# BenchExam.net
KiCad netlist of a schematic drawn in Altium Designer
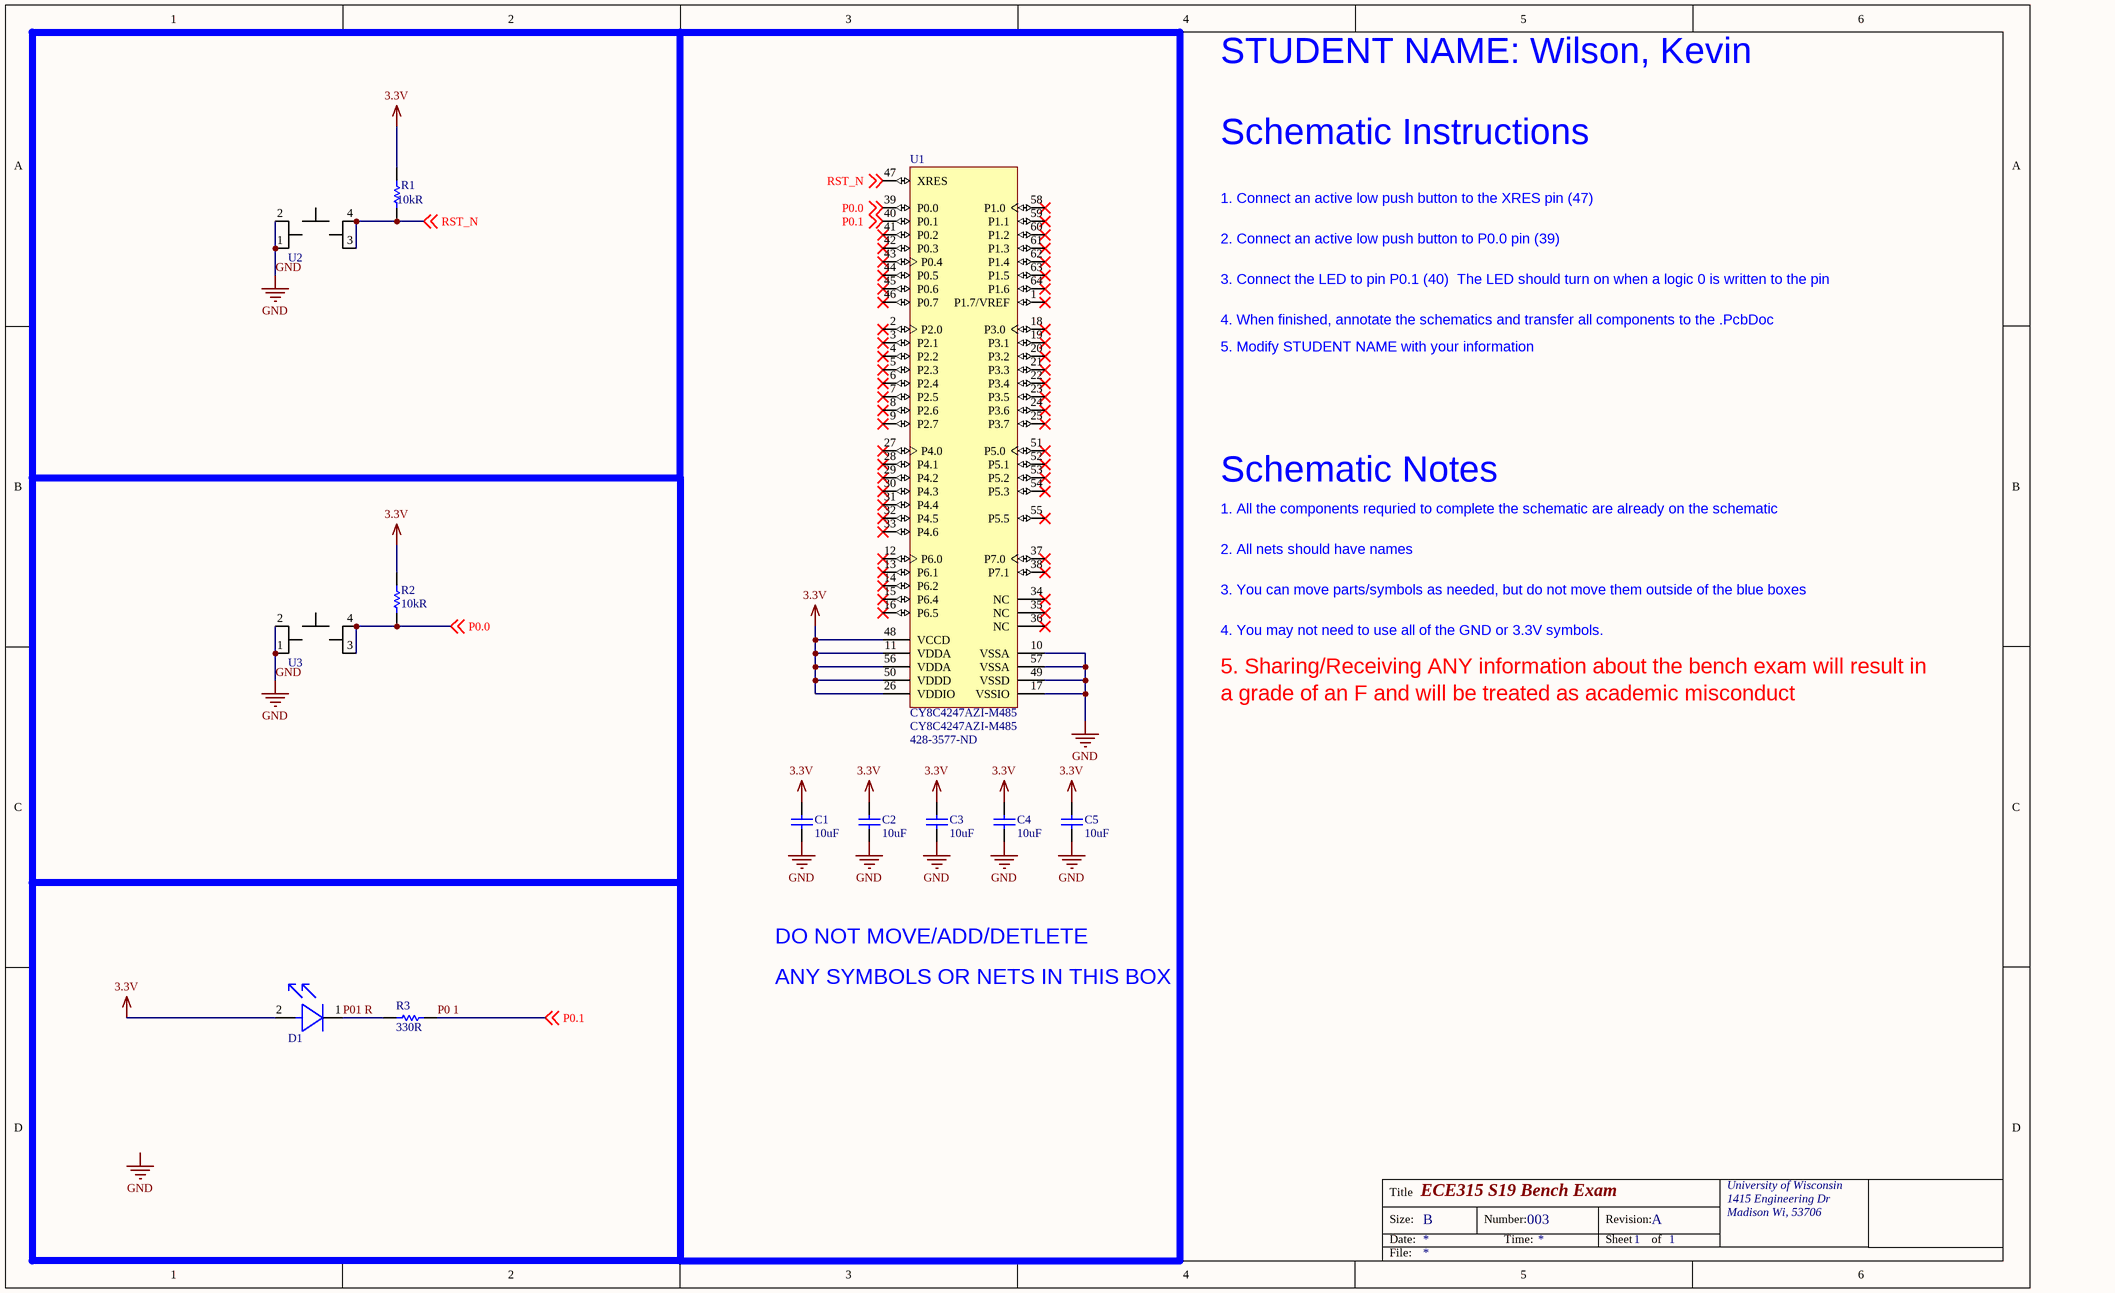
[diagram p0: BenchExam.SchDoc]

(export (version "E")
  (design (tool "Eeschema 10.0.6"))
  (components
    (comp (ref "C1")
      (value "10uF")
      (footprint "CAP_0805")
      (description "CAP CER 10UF 16V X7R 0805")
      (fields
        (field (name "TOLERANCE") "10%")
        (field (name "MANUFACTURER") "Samsung")
        (field (name "CAPACITANCE") "10uF")
      )
      (libsource (lib "BenchExam") (part "CAP_0805_U_010.00"))
    )
    (comp (ref "C2")
      (value "10uF")
      (footprint "CAP_0805")
      (description "CAP CER 10UF 16V X7R 0805")
      (fields
        (field (name "TOLERANCE") "10%")
        (field (name "MANUFACTURER") "Samsung")
        (field (name "CAPACITANCE") "10uF")
      )
      (libsource (lib "BenchExam") (part "CAP_0805_U_010.00"))
    )
    (comp (ref "C3")
      (value "10uF")
      (footprint "CAP_0805")
      (description "CAP CER 10UF 16V X7R 0805")
      (fields
        (field (name "TOLERANCE") "10%")
        (field (name "MANUFACTURER") "Samsung")
        (field (name "CAPACITANCE") "10uF")
      )
      (libsource (lib "BenchExam") (part "CAP_0805_U_010.00"))
    )
    (comp (ref "C4")
      (value "10uF")
      (footprint "CAP_0805")
      (description "CAP CER 10UF 16V X7R 0805")
      (fields
        (field (name "TOLERANCE") "10%")
        (field (name "MANUFACTURER") "Samsung")
        (field (name "CAPACITANCE") "10uF")
      )
      (libsource (lib "BenchExam") (part "CAP_0805_U_010.00"))
    )
    (comp (ref "C5")
      (value "10uF")
      (footprint "CAP_0805")
      (description "CAP CER 10UF 16V X7R 0805")
      (fields
        (field (name "TOLERANCE") "10%")
        (field (name "MANUFACTURER") "Samsung")
        (field (name "CAPACITANCE") "10uF")
      )
      (libsource (lib "BenchExam") (part "CAP_0805_U_010.00"))
    )
    (comp (ref "D1")
      (value "LED_BLUE_0805.1")
      (footprint "LED_BLU_0805")
      (description "LED 468NM BLUE CLEAR 0805 SMD")
      (fields
        (field (name "MANUFACTURER") "Vishay Lite-On")
        (field (name "MANUFACTURER PART NUMBER") "LTST-C171TBKT")
      )
      (libsource (lib "BenchExam") (part "LED_BLUE_0805.1"))
    )
    (comp (ref "R1")
      (value "10K")
      (footprint "RES_0805")
      (description "RES SMD 10K OHM 1% 1/8W 0805")
      (fields
        (field (name "MANUFACTURER PART NUMBER") "RMCF0805FT10K0")
        (field (name "TOLERANCE") "1%")
        (field (name "RESISTANCE") "10kR")
      )
      (libsource (lib "BenchExam") (part "RES_0805_K_010.00"))
    )
    (comp (ref "R2")
      (value "10K")
      (footprint "RES_0805")
      (description "RES SMD 10K OHM 1% 1/8W 0805")
      (fields
        (field (name "MANUFACTURER PART NUMBER") "RMCF0805FT10K0")
        (field (name "TOLERANCE") "1%")
        (field (name "RESISTANCE") "10kR")
      )
      (libsource (lib "BenchExam") (part "RES_0805_K_010.00"))
    )
    (comp (ref "R3")
      (value "330")
      (footprint "RES_0805")
      (description "RES SMD 330 OHM 1% 1/8W 0805")
      (fields
        (field (name "MANUFACTURER") "Stackpole Electronics")
        (field (name "MANUFACTURER PART NUMBER") "RMCF0805FT330R")
        (field (name "RESISTANCE") "330R")
      )
      (libsource (lib "BenchExam") (part "RES_0805_R_330.00"))
    )
    (comp (ref "U1")
      (value "CY8C4247AZI-M485")
      (footprint "CYP-AZ64_N")
      (fields
        (field (name "MANUFACTURER") "Cypress")
        (field (name "MANUFACTURER PART NUMBER") "CY8C4247AZI-M485")
        (field (name "SUPPLIER PART NUMBER") "428-3577-ND")
      )
      (libsource (lib "BenchExam") (part "CY8C4247AZI-M485"))
    )
    (comp (ref "U2")
      (value "SWITCH_6mm_6mm_smd")
      (footprint "SWITCH_6mm_6mm_smd")
      (description "SWITCH TACTILE SPST-NO 0.05A 12V")
      (fields
        (field (name "MANUFACTURER") "Carl Kammerling")
        (field (name "MANUFACTURER PART NUMBER") "PTS645SH50SMTR92LFS")
      )
      (libsource (lib "BenchExam") (part "SWITCH_6mm_6mm_smd"))
    )
    (comp (ref "U3")
      (value "SWITCH_6mm_6mm_smd")
      (footprint "SWITCH_6mm_6mm_smd")
      (description "SWITCH TACTILE SPST-NO 0.05A 12V")
      (fields
        (field (name "MANUFACTURER") "Carl Kammerling")
        (field (name "MANUFACTURER PART NUMBER") "PTS645SH50SMTR92LFS")
      )
      (libsource (lib "BenchExam") (part "SWITCH_6mm_6mm_smd"))
    )
  )
  (nets
    (net (code "1") (name "/P01 R") (class "Default")
      (node (ref "D1") (pin "1") (pinfunction "Cathode_1") (pintype "passive"))
      (node (ref "R3") (pin "1") (pinfunction "1_1") (pintype "passive"))
    )
    (net (code "2") (name "3.3V") (class "Default")
      (node (ref "C1") (pin "2") (pinfunction "2_2") (pintype "passive"))
      (node (ref "C2") (pin "2") (pinfunction "2_2") (pintype "passive"))
      (node (ref "C3") (pin "2") (pinfunction "2_2") (pintype "passive"))
      (node (ref "C4") (pin "2") (pinfunction "2_2") (pintype "passive"))
      (node (ref "C5") (pin "2") (pinfunction "2_2") (pintype "passive"))
      (node (ref "D1") (pin "2") (pinfunction "Anode_2") (pintype "passive"))
      (node (ref "R1") (pin "1") (pinfunction "1_1") (pintype "passive"))
      (node (ref "R2") (pin "2") (pinfunction "2_2") (pintype "passive"))
      (node (ref "U1") (pin "11") (pinfunction "VDDA_11") (pintype "power_in"))
      (node (ref "U1") (pin "26") (pinfunction "VDDIO_26") (pintype "power_in"))
      (node (ref "U1") (pin "48") (pinfunction "VCCD_48") (pintype "power_in"))
      (node (ref "U1") (pin "50") (pinfunction "VDDD_50") (pintype "power_in"))
      (node (ref "U1") (pin "56") (pinfunction "VDDA_56") (pintype "power_in"))
    )
    (net (code "3") (name "GND") (class "Default")
      (node (ref "C1") (pin "1") (pinfunction "1_1") (pintype "passive"))
      (node (ref "C2") (pin "1") (pinfunction "1_1") (pintype "passive"))
      (node (ref "C3") (pin "1") (pinfunction "1_1") (pintype "passive"))
      (node (ref "C4") (pin "1") (pinfunction "1_1") (pintype "passive"))
      (node (ref "C5") (pin "1") (pinfunction "1_1") (pintype "passive"))
      (node (ref "U1") (pin "10") (pinfunction "VSSA_10") (pintype "power_in"))
      (node (ref "U1") (pin "17") (pinfunction "VSSIO_17") (pintype "power_in"))
      (node (ref "U1") (pin "49") (pinfunction "VSSD_49") (pintype "power_in"))
      (node (ref "U1") (pin "57") (pinfunction "VSSA_57") (pintype "power_in"))
      (node (ref "U2") (pin "1") (pinfunction "1_1") (pintype "passive"))
      (node (ref "U2") (pin "2") (pinfunction "2_2") (pintype "passive"))
      (node (ref "U3") (pin "1") (pinfunction "1_1") (pintype "passive"))
      (node (ref "U3") (pin "2") (pinfunction "2_2") (pintype "passive"))
    )
    (net (code "4") (name "P0.0") (class "Default")
      (node (ref "R2") (pin "1") (pinfunction "1_1") (pintype "passive"))
      (node (ref "U1") (pin "39") (pinfunction "P0.0_39") (pintype "bidirectional"))
      (node (ref "U3") (pin "3") (pinfunction "3_3") (pintype "passive"))
      (node (ref "U3") (pin "4") (pinfunction "VCCIO_4") (pintype "passive"))
    )
    (net (code "5") (name "P0.1") (class "Default")
      (node (ref "R3") (pin "2") (pinfunction "2_2") (pintype "passive"))
      (node (ref "U1") (pin "40") (pinfunction "P0.1_40") (pintype "bidirectional"))
    )
    (net (code "6") (name "RST_N") (class "Default")
      (node (ref "R1") (pin "2") (pinfunction "2_2") (pintype "passive"))
      (node (ref "U1") (pin "47") (pinfunction "XRES_47") (pintype "bidirectional"))
      (node (ref "U2") (pin "3") (pinfunction "3_3") (pintype "passive"))
      (node (ref "U2") (pin "4") (pinfunction "VCCIO_4") (pintype "passive"))
    )
    (net (code "7") (name "unconnected-(U1-NC-Pad34)") (class "Default")
      (node (ref "U1") (pin "34") (pinfunction "NC_34") (pintype "passive+no_connect"))
    )
    (net (code "8") (name "unconnected-(U1-NC-Pad35)") (class "Default")
      (node (ref "U1") (pin "35") (pinfunction "NC_35") (pintype "passive+no_connect"))
    )
    (net (code "9") (name "unconnected-(U1-NC-Pad36)") (class "Default")
      (node (ref "U1") (pin "36") (pinfunction "NC_36") (pintype "passive+no_connect"))
    )
    (net (code "10") (name "unconnected-(U1-P0.2-Pad41)") (class "Default")
      (node (ref "U1") (pin "41") (pinfunction "P0.2_41") (pintype "bidirectional+no_connect"))
    )
    (net (code "11") (name "unconnected-(U1-P0.3-Pad42)") (class "Default")
      (node (ref "U1") (pin "42") (pinfunction "P0.3_42") (pintype "bidirectional+no_connect"))
    )
    (net (code "12") (name "unconnected-(U1-P0.4-Pad43)") (class "Default")
      (node (ref "U1") (pin "43") (pinfunction "P0.4_43") (pintype "bidirectional+no_connect"))
    )
    (net (code "13") (name "unconnected-(U1-P0.5-Pad44)") (class "Default")
      (node (ref "U1") (pin "44") (pinfunction "P0.5_44") (pintype "bidirectional+no_connect"))
    )
    (net (code "14") (name "unconnected-(U1-P0.6-Pad45)") (class "Default")
      (node (ref "U1") (pin "45") (pinfunction "P0.6_45") (pintype "bidirectional+no_connect"))
    )
    (net (code "15") (name "unconnected-(U1-P0.7-Pad46)") (class "Default")
      (node (ref "U1") (pin "46") (pinfunction "P0.7_46") (pintype "bidirectional+no_connect"))
    )
    (net (code "16") (name "unconnected-(U1-P1.0-Pad58)") (class "Default")
      (node (ref "U1") (pin "58") (pinfunction "P1.0_58") (pintype "bidirectional+no_connect"))
    )
    (net (code "17") (name "unconnected-(U1-P1.1-Pad59)") (class "Default")
      (node (ref "U1") (pin "59") (pinfunction "P1.1_59") (pintype "bidirectional+no_connect"))
    )
    (net (code "18") (name "unconnected-(U1-P1.2-Pad60)") (class "Default")
      (node (ref "U1") (pin "60") (pinfunction "P1.2_60") (pintype "bidirectional+no_connect"))
    )
    (net (code "19") (name "unconnected-(U1-P1.3-Pad61)") (class "Default")
      (node (ref "U1") (pin "61") (pinfunction "P1.3_61") (pintype "bidirectional+no_connect"))
    )
    (net (code "20") (name "unconnected-(U1-P1.4-Pad62)") (class "Default")
      (node (ref "U1") (pin "62") (pinfunction "P1.4_62") (pintype "bidirectional+no_connect"))
    )
    (net (code "21") (name "unconnected-(U1-P1.5-Pad63)") (class "Default")
      (node (ref "U1") (pin "63") (pinfunction "P1.5_63") (pintype "bidirectional+no_connect"))
    )
    (net (code "22") (name "unconnected-(U1-P1.6-Pad64)") (class "Default")
      (node (ref "U1") (pin "64") (pinfunction "P1.6_64") (pintype "bidirectional+no_connect"))
    )
    (net (code "23") (name "unconnected-(U1-P1.7{slash}VREF-Pad1)") (class "Default")
      (node (ref "U1") (pin "1") (pinfunction "P1.7/VREF_1") (pintype "bidirectional+no_connect"))
    )
    (net (code "24") (name "unconnected-(U1-P2.0-Pad2)") (class "Default")
      (node (ref "U1") (pin "2") (pinfunction "P2.0_2") (pintype "bidirectional+no_connect"))
    )
    (net (code "25") (name "unconnected-(U1-P2.1-Pad3)") (class "Default")
      (node (ref "U1") (pin "3") (pinfunction "P2.1_3") (pintype "bidirectional+no_connect"))
    )
    (net (code "26") (name "unconnected-(U1-P2.2-Pad4)") (class "Default")
      (node (ref "U1") (pin "4") (pinfunction "P2.2_4") (pintype "bidirectional+no_connect"))
    )
    (net (code "27") (name "unconnected-(U1-P2.3-Pad5)") (class "Default")
      (node (ref "U1") (pin "5") (pinfunction "P2.3_5") (pintype "bidirectional+no_connect"))
    )
    (net (code "28") (name "unconnected-(U1-P2.4-Pad6)") (class "Default")
      (node (ref "U1") (pin "6") (pinfunction "P2.4_6") (pintype "bidirectional+no_connect"))
    )
    (net (code "29") (name "unconnected-(U1-P2.5-Pad7)") (class "Default")
      (node (ref "U1") (pin "7") (pinfunction "P2.5_7") (pintype "bidirectional+no_connect"))
    )
    (net (code "30") (name "unconnected-(U1-P2.6-Pad8)") (class "Default")
      (node (ref "U1") (pin "8") (pinfunction "P2.6_8") (pintype "bidirectional+no_connect"))
    )
    (net (code "31") (name "unconnected-(U1-P2.7-Pad9)") (class "Default")
      (node (ref "U1") (pin "9") (pinfunction "P2.7_9") (pintype "bidirectional+no_connect"))
    )
    (net (code "32") (name "unconnected-(U1-P3.0-Pad18)") (class "Default")
      (node (ref "U1") (pin "18") (pinfunction "P3.0_18") (pintype "bidirectional+no_connect"))
    )
    (net (code "33") (name "unconnected-(U1-P3.1-Pad19)") (class "Default")
      (node (ref "U1") (pin "19") (pinfunction "P3.1_19") (pintype "bidirectional+no_connect"))
    )
    (net (code "34") (name "unconnected-(U1-P3.2-Pad20)") (class "Default")
      (node (ref "U1") (pin "20") (pinfunction "P3.2_20") (pintype "bidirectional+no_connect"))
    )
    (net (code "35") (name "unconnected-(U1-P3.3-Pad21)") (class "Default")
      (node (ref "U1") (pin "21") (pinfunction "P3.3_21") (pintype "bidirectional+no_connect"))
    )
    (net (code "36") (name "unconnected-(U1-P3.4-Pad22)") (class "Default")
      (node (ref "U1") (pin "22") (pinfunction "P3.4_22") (pintype "bidirectional+no_connect"))
    )
    (net (code "37") (name "unconnected-(U1-P3.5-Pad23)") (class "Default")
      (node (ref "U1") (pin "23") (pinfunction "P3.5_23") (pintype "bidirectional+no_connect"))
    )
    (net (code "38") (name "unconnected-(U1-P3.6-Pad24)") (class "Default")
      (node (ref "U1") (pin "24") (pinfunction "P3.6_24") (pintype "bidirectional+no_connect"))
    )
    (net (code "39") (name "unconnected-(U1-P3.7-Pad25)") (class "Default")
      (node (ref "U1") (pin "25") (pinfunction "P3.7_25") (pintype "bidirectional+no_connect"))
    )
    (net (code "40") (name "unconnected-(U1-P4.0-Pad27)") (class "Default")
      (node (ref "U1") (pin "27") (pinfunction "P4.0_27") (pintype "bidirectional+no_connect"))
    )
    (net (code "41") (name "unconnected-(U1-P4.1-Pad28)") (class "Default")
      (node (ref "U1") (pin "28") (pinfunction "P4.1_28") (pintype "bidirectional+no_connect"))
    )
    (net (code "42") (name "unconnected-(U1-P4.2-Pad29)") (class "Default")
      (node (ref "U1") (pin "29") (pinfunction "P4.2_29") (pintype "bidirectional+no_connect"))
    )
    (net (code "43") (name "unconnected-(U1-P4.3-Pad30)") (class "Default")
      (node (ref "U1") (pin "30") (pinfunction "P4.3_30") (pintype "bidirectional+no_connect"))
    )
    (net (code "44") (name "unconnected-(U1-P4.4-Pad31)") (class "Default")
      (node (ref "U1") (pin "31") (pinfunction "P4.4_31") (pintype "bidirectional+no_connect"))
    )
    (net (code "45") (name "unconnected-(U1-P4.5-Pad32)") (class "Default")
      (node (ref "U1") (pin "32") (pinfunction "P4.5_32") (pintype "bidirectional+no_connect"))
    )
    (net (code "46") (name "unconnected-(U1-P4.6-Pad33)") (class "Default")
      (node (ref "U1") (pin "33") (pinfunction "P4.6_33") (pintype "bidirectional+no_connect"))
    )
    (net (code "47") (name "unconnected-(U1-P5.0-Pad51)") (class "Default")
      (node (ref "U1") (pin "51") (pinfunction "P5.0_51") (pintype "bidirectional+no_connect"))
    )
    (net (code "48") (name "unconnected-(U1-P5.1-Pad52)") (class "Default")
      (node (ref "U1") (pin "52") (pinfunction "P5.1_52") (pintype "bidirectional+no_connect"))
    )
    (net (code "49") (name "unconnected-(U1-P5.2-Pad53)") (class "Default")
      (node (ref "U1") (pin "53") (pinfunction "P5.2_53") (pintype "bidirectional+no_connect"))
    )
    (net (code "50") (name "unconnected-(U1-P5.3-Pad54)") (class "Default")
      (node (ref "U1") (pin "54") (pinfunction "P5.3_54") (pintype "bidirectional+no_connect"))
    )
    (net (code "51") (name "unconnected-(U1-P5.5-Pad55)") (class "Default")
      (node (ref "U1") (pin "55") (pinfunction "P5.5_55") (pintype "bidirectional+no_connect"))
    )
    (net (code "52") (name "unconnected-(U1-P6.0-Pad12)") (class "Default")
      (node (ref "U1") (pin "12") (pinfunction "P6.0_12") (pintype "bidirectional+no_connect"))
    )
    (net (code "53") (name "unconnected-(U1-P6.1-Pad13)") (class "Default")
      (node (ref "U1") (pin "13") (pinfunction "P6.1_13") (pintype "bidirectional+no_connect"))
    )
    (net (code "54") (name "unconnected-(U1-P6.2-Pad14)") (class "Default")
      (node (ref "U1") (pin "14") (pinfunction "P6.2_14") (pintype "bidirectional+no_connect"))
    )
    (net (code "55") (name "unconnected-(U1-P6.4-Pad15)") (class "Default")
      (node (ref "U1") (pin "15") (pinfunction "P6.4_15") (pintype "bidirectional+no_connect"))
    )
    (net (code "56") (name "unconnected-(U1-P6.5-Pad16)") (class "Default")
      (node (ref "U1") (pin "16") (pinfunction "P6.5_16") (pintype "bidirectional+no_connect"))
    )
    (net (code "57") (name "unconnected-(U1-P7.0-Pad37)") (class "Default")
      (node (ref "U1") (pin "37") (pinfunction "P7.0_37") (pintype "bidirectional+no_connect"))
    )
    (net (code "58") (name "unconnected-(U1-P7.1-Pad38)") (class "Default")
      (node (ref "U1") (pin "38") (pinfunction "P7.1_38") (pintype "bidirectional+no_connect"))
    )
  )
)
